# SilentStepStick-TMC5160_v14.net
KiCad netlist of a schematic drawn in EAGLE
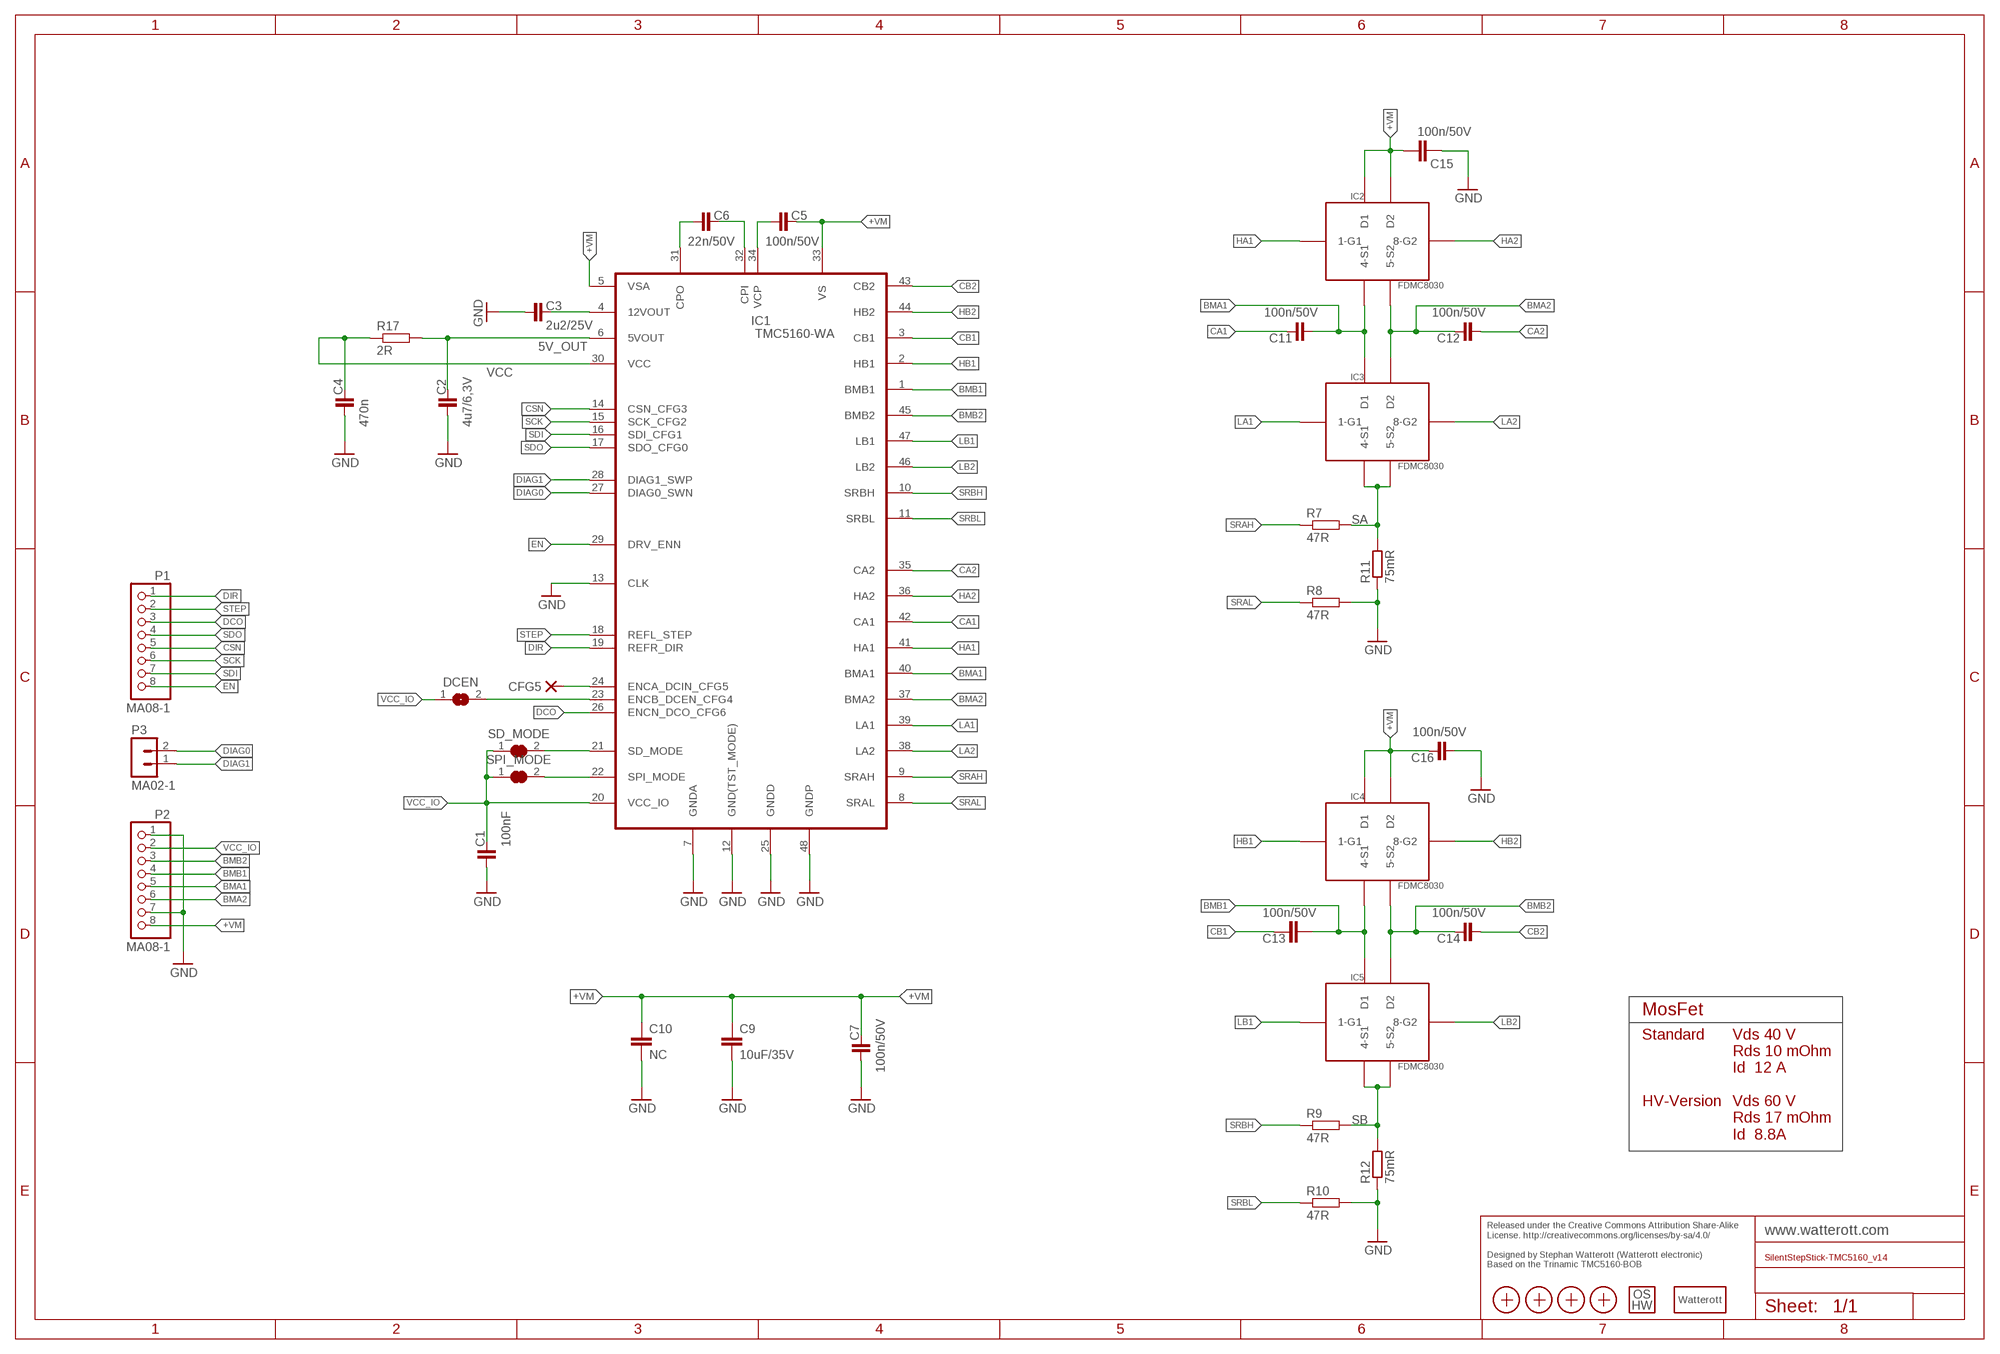
[diagram p0: schematic, sheet 1]

(export (version "E")
  (design (tool "Eeschema 10.0.6"))
  (components
    (comp (ref "C1")
      (value "100nF")
      (footprint "eagle-import:C0402")
      (libsource (lib "eagle-import") (part "CAPACITOR-0402"))
    )
    (comp (ref "C2")
      (value "4u7/6,3V")
      (footprint "eagle-import:C0402")
      (libsource (lib "eagle-import") (part "CAPACITOR-0402"))
    )
    (comp (ref "C3")
      (value "2u2/25V")
      (footprint "eagle-import:C0402")
      (libsource (lib "eagle-import") (part "CAPACITOR-0402"))
    )
    (comp (ref "C4")
      (value "470n")
      (footprint "eagle-import:C0402")
      (libsource (lib "eagle-import") (part "CAPACITOR-0402"))
    )
    (comp (ref "C5")
      (value "100n/50V")
      (footprint "eagle-import:C0402")
      (libsource (lib "eagle-import") (part "CAPACITOR-0402"))
    )
    (comp (ref "C6")
      (value "22n/50V")
      (footprint "eagle-import:C0402")
      (libsource (lib "eagle-import") (part "CAPACITOR-0402"))
    )
    (comp (ref "C7")
      (value "100n/50V")
      (footprint "eagle-import:C0402")
      (libsource (lib "eagle-import") (part "CAPACITOR-0402"))
    )
    (comp (ref "C9")
      (value "10uF/35V")
      (footprint "eagle-import:C0805")
      (libsource (lib "eagle-import") (part "C-EUC0805"))
    )
    (comp (ref "C10")
      (value "NC")
      (footprint "eagle-import:C0805")
      (libsource (lib "eagle-import") (part "C-EUC0805"))
    )
    (comp (ref "C11")
      (value "100n/50V")
      (footprint "eagle-import:C0402")
      (libsource (lib "eagle-import") (part "CAPACITOR-0402"))
    )
    (comp (ref "C12")
      (value "100n/50V")
      (footprint "eagle-import:C0402")
      (libsource (lib "eagle-import") (part "CAPACITOR-0402"))
    )
    (comp (ref "C13")
      (value "100n/50V")
      (footprint "eagle-import:C0402")
      (libsource (lib "eagle-import") (part "C-EUC0402"))
    )
    (comp (ref "C14")
      (value "100n/50V")
      (footprint "eagle-import:C0402")
      (libsource (lib "eagle-import") (part "CAPACITOR-0402"))
    )
    (comp (ref "C15")
      (value "100n/50V")
      (footprint "eagle-import:C0402")
      (libsource (lib "eagle-import") (part "C-EUC0402"))
    )
    (comp (ref "C16")
      (value "100n/50V")
      (footprint "eagle-import:C0402")
      (libsource (lib "eagle-import") (part "CAPACITOR-0402"))
    )
    (comp (ref "CFG5")
      (value "PAD-0.7_NC")
      (footprint "eagle-import:PAD-0.7_NC")
      (libsource (lib "eagle-import") (part "PAD-0.7_NC"))
    )
    (comp (ref "DCEN")
      (value "JUMPER2-0402-NC")
      (footprint "eagle-import:JUMPER2-0402_NC")
      (libsource (lib "eagle-import") (part "JUMPER2-0402-NC"))
    )
    (comp (ref "IC1")
      (value "TMC5160-WA")
      (footprint "eagle-import:VQFN56(47)_8.0X8.0X0.9MM_0.5P_EP")
      (libsource (lib "eagle-import") (part "TMC5160-WA"))
    )
    (comp (ref "IC2")
      (value "FDMC8030")
      (footprint "eagle-import:8-POWERWDFN")
      (libsource (lib "eagle-import") (part "FDMC8030"))
    )
    (comp (ref "IC3")
      (value "FDMC8030")
      (footprint "eagle-import:8-POWERWDFN")
      (libsource (lib "eagle-import") (part "FDMC8030"))
    )
    (comp (ref "IC4")
      (value "FDMC8030")
      (footprint "eagle-import:8-POWERWDFN")
      (libsource (lib "eagle-import") (part "FDMC8030"))
    )
    (comp (ref "IC5")
      (value "FDMC8030")
      (footprint "eagle-import:8-POWERWDFN")
      (libsource (lib "eagle-import") (part "FDMC8030"))
    )
    (comp (ref "LOGO1")
      (value "LOGO_SPARK-2")
      (footprint "eagle-import:SPARK_2MM")
      (libsource (lib "eagle-import") (part "LOGO_SPARK-2"))
    )
    (comp (ref "LOGO2")
      (value "LOGO_OSHW-2")
      (footprint "eagle-import:OSHW_2MM")
      (libsource (lib "eagle-import") (part "LOGO_OSHW-2"))
    )
    (comp (ref "P1")
      (value "MA08-1")
      (footprint "eagle-import:1X08-S")
      (libsource (lib "eagle-import") (part "PINHD-1X08_2.54-S"))
    )
    (comp (ref "P2")
      (value "MA08-1")
      (footprint "eagle-import:1X08-S")
      (libsource (lib "eagle-import") (part "PINHD-1X08_2.54-S"))
    )
    (comp (ref "P3")
      (value "MA02-1")
      (footprint "eagle-import:MA02-1")
      (libsource (lib "eagle-import") (part "MA02-1"))
    )
    (comp (ref "R7")
      (value "47R")
      (footprint "eagle-import:C0402")
      (libsource (lib "eagle-import") (part "RESISTOR-0402"))
    )
    (comp (ref "R8")
      (value "47R")
      (footprint "eagle-import:C0402")
      (libsource (lib "eagle-import") (part "RESISTOR-0402"))
    )
    (comp (ref "R9")
      (value "47R")
      (footprint "eagle-import:C0402")
      (libsource (lib "eagle-import") (part "RESISTOR-0402"))
    )
    (comp (ref "R10")
      (value "47R")
      (footprint "eagle-import:C0402")
      (libsource (lib "eagle-import") (part "RESISTOR-0402"))
    )
    (comp (ref "R11")
      (value "75mR")
      (footprint "eagle-import:R1206")
      (libsource (lib "eagle-import") (part "R-EU_R1206"))
    )
    (comp (ref "R12")
      (value "75mR")
      (footprint "eagle-import:R1206")
      (libsource (lib "eagle-import") (part "R-EU_R1206"))
    )
    (comp (ref "R17")
      (value "2R")
      (footprint "eagle-import:C0402")
      (libsource (lib "eagle-import") (part "RESISTOR-0402"))
    )
    (comp (ref "SD_MODE")
      (value "JUMPER2-0402-NC")
      (footprint "eagle-import:JUMPER2-0402_NC")
      (libsource (lib "eagle-import") (part "JUMPER2-0402-NC"))
    )
    (comp (ref "SPI_MODE")
      (value "JUMPER2-0402-NC")
      (footprint "eagle-import:JUMPER2-0402_NC")
      (libsource (lib "eagle-import") (part "JUMPER2-0402-NC"))
    )
    (comp (ref "X1")
      (value "PASSER-04")
      (footprint "eagle-import:PASSER_04MM")
      (libsource (lib "eagle-import") (part "PASSER-04"))
    )
    (comp (ref "X2")
      (value "PASSER-04")
      (footprint "eagle-import:PASSER_04MM")
      (libsource (lib "eagle-import") (part "PASSER-04"))
    )
    (comp (ref "X3")
      (value "PASSER-04")
      (footprint "eagle-import:PASSER_04MM")
      (libsource (lib "eagle-import") (part "PASSER-04"))
    )
    (comp (ref "X4")
      (value "PASSER-04")
      (footprint "eagle-import:PASSER_04MM")
      (libsource (lib "eagle-import") (part "PASSER-04"))
    )
  )
  (nets
    (net (code "1") (name "+VM") (class "Default")
      (node (ref "C10") (pin "1") (pinfunction "1_1") (pintype "passive"))
      (node (ref "C15") (pin "2") (pinfunction "2_2") (pintype "passive"))
      (node (ref "C16") (pin "2") (pinfunction "2_2") (pintype "passive"))
      (node (ref "C5") (pin "2") (pinfunction "2_2") (pintype "passive"))
      (node (ref "C7") (pin "2") (pinfunction "2_2") (pintype "passive"))
      (node (ref "C9") (pin "1") (pinfunction "1_1") (pintype "passive"))
      (node (ref "IC1") (pin "33") (pinfunction "VS_33") (pintype "power_in"))
      (node (ref "IC1") (pin "5") (pinfunction "VSA_5") (pintype "power_in"))
      (node (ref "IC2") (pin "P$D1") (pinfunction "D1_P$D1") (pintype "bidirectional"))
      (node (ref "IC2") (pin "P$D2") (pinfunction "D2_P$D2") (pintype "bidirectional"))
      (node (ref "IC4") (pin "P$D1") (pinfunction "D1_P$D1") (pintype "bidirectional"))
      (node (ref "IC4") (pin "P$D2") (pinfunction "D2_P$D2") (pintype "bidirectional"))
      (node (ref "P2") (pin "8") (pinfunction "8_8") (pintype "passive"))
    )
    (net (code "2") (name "/5V_OUT") (class "Default")
      (node (ref "C2") (pin "2") (pinfunction "2_2") (pintype "passive"))
      (node (ref "IC1") (pin "6") (pinfunction "5VOUT_6") (pintype "bidirectional"))
      (node (ref "R17") (pin "2") (pinfunction "2_2") (pintype "passive"))
    )
    (net (code "3") (name "/SA") (class "Default")
      (node (ref "IC3") (pin "P$4") (pinfunction "4-S1_P$4") (pintype "bidirectional"))
      (node (ref "IC3") (pin "P$5") (pinfunction "5-S2_P$5") (pintype "bidirectional"))
      (node (ref "R11") (pin "2") (pinfunction "2_2") (pintype "passive"))
      (node (ref "R7") (pin "2") (pinfunction "2_2") (pintype "passive"))
    )
    (net (code "4") (name "/SB") (class "Default")
      (node (ref "IC5") (pin "P$4") (pinfunction "4-S1_P$4") (pintype "bidirectional"))
      (node (ref "IC5") (pin "P$5") (pinfunction "5-S2_P$5") (pintype "bidirectional"))
      (node (ref "R12") (pin "2") (pinfunction "2_2") (pintype "passive"))
      (node (ref "R9") (pin "2") (pinfunction "2_2") (pintype "passive"))
    )
    (net (code "5") (name "/VCC") (class "Default")
      (node (ref "C4") (pin "2") (pinfunction "2_2") (pintype "passive"))
      (node (ref "IC1") (pin "30") (pinfunction "VCC_30") (pintype "power_in"))
      (node (ref "R17") (pin "1") (pinfunction "1_1") (pintype "passive"))
    )
    (net (code "6") (name "BMA1") (class "Default")
      (node (ref "C11") (pin "1") (pinfunction "1_1") (pintype "passive"))
      (node (ref "IC1") (pin "40") (pinfunction "BMA1_40") (pintype "input"))
      (node (ref "IC2") (pin "P$4") (pinfunction "4-S1_P$4") (pintype "bidirectional"))
      (node (ref "IC3") (pin "P$D1") (pinfunction "D1_P$D1") (pintype "bidirectional"))
      (node (ref "P2") (pin "5") (pinfunction "5_5") (pintype "passive"))
    )
    (net (code "7") (name "BMA2") (class "Default")
      (node (ref "C12") (pin "2") (pinfunction "2_2") (pintype "passive"))
      (node (ref "IC1") (pin "37") (pinfunction "BMA2_37") (pintype "input"))
      (node (ref "IC2") (pin "P$5") (pinfunction "5-S2_P$5") (pintype "bidirectional"))
      (node (ref "IC3") (pin "P$D2") (pinfunction "D2_P$D2") (pintype "bidirectional"))
      (node (ref "P2") (pin "6") (pinfunction "6_6") (pintype "passive"))
    )
    (net (code "8") (name "BMB1") (class "Default")
      (node (ref "C13") (pin "1") (pinfunction "1_1") (pintype "passive"))
      (node (ref "IC1") (pin "1") (pinfunction "BMB1_1") (pintype "input"))
      (node (ref "IC4") (pin "P$4") (pinfunction "4-S1_P$4") (pintype "bidirectional"))
      (node (ref "IC5") (pin "P$D1") (pinfunction "D1_P$D1") (pintype "bidirectional"))
      (node (ref "P2") (pin "4") (pinfunction "4_4") (pintype "passive"))
    )
    (net (code "9") (name "BMB2") (class "Default")
      (node (ref "C14") (pin "2") (pinfunction "2_2") (pintype "passive"))
      (node (ref "IC1") (pin "45") (pinfunction "BMB2_45") (pintype "input"))
      (node (ref "IC4") (pin "P$5") (pinfunction "5-S2_P$5") (pintype "bidirectional"))
      (node (ref "IC5") (pin "P$D2") (pinfunction "D2_P$D2") (pintype "bidirectional"))
      (node (ref "P2") (pin "3") (pinfunction "3_3") (pintype "passive"))
    )
    (net (code "10") (name "CA1") (class "Default")
      (node (ref "C11") (pin "2") (pinfunction "2_2") (pintype "passive"))
      (node (ref "IC1") (pin "42") (pinfunction "CA1_42") (pintype "input"))
    )
    (net (code "11") (name "CA2") (class "Default")
      (node (ref "C12") (pin "1") (pinfunction "1_1") (pintype "passive"))
      (node (ref "IC1") (pin "35") (pinfunction "CA2_35") (pintype "input"))
    )
    (net (code "12") (name "CB1") (class "Default")
      (node (ref "C13") (pin "2") (pinfunction "2_2") (pintype "passive"))
      (node (ref "IC1") (pin "3") (pinfunction "CB1_3") (pintype "input"))
    )
    (net (code "13") (name "CB2") (class "Default")
      (node (ref "C14") (pin "1") (pinfunction "1_1") (pintype "passive"))
      (node (ref "IC1") (pin "43") (pinfunction "CB2_43") (pintype "input"))
    )
    (net (code "14") (name "CSN") (class "Default")
      (node (ref "IC1") (pin "14") (pinfunction "CSN_CFG3_14") (pintype "input"))
      (node (ref "P1") (pin "5") (pinfunction "5_5") (pintype "passive"))
    )
    (net (code "15") (name "DCO") (class "Default")
      (node (ref "IC1") (pin "26") (pinfunction "ENCN_DCO_CFG6_26") (pintype "bidirectional"))
      (node (ref "P1") (pin "3") (pinfunction "3_3") (pintype "passive"))
    )
    (net (code "16") (name "DIAG0") (class "Default")
      (node (ref "IC1") (pin "27") (pinfunction "DIAG0_SWN_27") (pintype "bidirectional"))
      (node (ref "P3") (pin "2") (pinfunction "2_2") (pintype "passive"))
    )
    (net (code "17") (name "DIAG1") (class "Default")
      (node (ref "IC1") (pin "28") (pinfunction "DIAG1_SWP_28") (pintype "bidirectional"))
      (node (ref "P3") (pin "1") (pinfunction "1_1") (pintype "passive"))
    )
    (net (code "18") (name "DIR") (class "Default")
      (node (ref "IC1") (pin "19") (pinfunction "REFR_DIR_19") (pintype "input"))
      (node (ref "P1") (pin "1") (pinfunction "1_1") (pintype "passive"))
    )
    (net (code "19") (name "EN") (class "Default")
      (node (ref "IC1") (pin "29") (pinfunction "DRV_ENN_29") (pintype "input"))
      (node (ref "P1") (pin "8") (pinfunction "8_8") (pintype "passive"))
    )
    (net (code "20") (name "GND") (class "Default")
      (node (ref "C1") (pin "1") (pinfunction "1_1") (pintype "passive"))
      (node (ref "C10") (pin "2") (pinfunction "2_2") (pintype "passive"))
      (node (ref "C15") (pin "1") (pinfunction "1_1") (pintype "passive"))
      (node (ref "C16") (pin "1") (pinfunction "1_1") (pintype "passive"))
      (node (ref "C2") (pin "1") (pinfunction "1_1") (pintype "passive"))
      (node (ref "C3") (pin "1") (pinfunction "1_1") (pintype "passive"))
      (node (ref "C4") (pin "1") (pinfunction "1_1") (pintype "passive"))
      (node (ref "C7") (pin "1") (pinfunction "1_1") (pintype "passive"))
      (node (ref "C9") (pin "2") (pinfunction "2_2") (pintype "passive"))
      (node (ref "IC1") (pin "12") (pinfunction "GND(TST_MODE)_12") (pintype "input"))
      (node (ref "IC1") (pin "13") (pinfunction "CLK_13") (pintype "input"))
      (node (ref "IC1") (pin "25") (pinfunction "GNDD_25") (pintype "power_in"))
      (node (ref "IC1") (pin "48") (pinfunction "GNDP_48") (pintype "power_in"))
      (node (ref "IC1") (pin "7") (pinfunction "GNDA_7") (pintype "power_in"))
      (node (ref "P2") (pin "1") (pinfunction "1_1") (pintype "passive"))
      (node (ref "P2") (pin "7") (pinfunction "7_7") (pintype "passive"))
      (node (ref "R10") (pin "2") (pinfunction "2_2") (pintype "passive"))
      (node (ref "R11") (pin "1") (pinfunction "1_1") (pintype "passive"))
      (node (ref "R12") (pin "1") (pinfunction "1_1") (pintype "passive"))
      (node (ref "R8") (pin "2") (pinfunction "2_2") (pintype "passive"))
    )
    (net (code "21") (name "HA1") (class "Default")
      (node (ref "IC1") (pin "41") (pinfunction "HA1_41") (pintype "output"))
      (node (ref "IC2") (pin "P$1") (pinfunction "1-G1_P$1") (pintype "bidirectional"))
    )
    (net (code "22") (name "HA2") (class "Default")
      (node (ref "IC1") (pin "36") (pinfunction "HA2_36") (pintype "output"))
      (node (ref "IC2") (pin "P$8") (pinfunction "8-G2_P$8") (pintype "bidirectional"))
    )
    (net (code "23") (name "HB1") (class "Default")
      (node (ref "IC1") (pin "2") (pinfunction "HB1_2") (pintype "output"))
      (node (ref "IC4") (pin "P$1") (pinfunction "1-G1_P$1") (pintype "bidirectional"))
    )
    (net (code "24") (name "HB2") (class "Default")
      (node (ref "IC1") (pin "44") (pinfunction "HB2_44") (pintype "output"))
      (node (ref "IC4") (pin "P$8") (pinfunction "8-G2_P$8") (pintype "bidirectional"))
    )
    (net (code "25") (name "LA1") (class "Default")
      (node (ref "IC1") (pin "39") (pinfunction "LA1_39") (pintype "output"))
      (node (ref "IC3") (pin "P$1") (pinfunction "1-G1_P$1") (pintype "bidirectional"))
    )
    (net (code "26") (name "LA2") (class "Default")
      (node (ref "IC1") (pin "38") (pinfunction "LA2_38") (pintype "output"))
      (node (ref "IC3") (pin "P$8") (pinfunction "8-G2_P$8") (pintype "bidirectional"))
    )
    (net (code "27") (name "LB1") (class "Default")
      (node (ref "IC1") (pin "47") (pinfunction "LB1_47") (pintype "output"))
      (node (ref "IC5") (pin "P$1") (pinfunction "1-G1_P$1") (pintype "bidirectional"))
    )
    (net (code "28") (name "LB2") (class "Default")
      (node (ref "IC1") (pin "46") (pinfunction "LB2_46") (pintype "output"))
      (node (ref "IC5") (pin "P$8") (pinfunction "8-G2_P$8") (pintype "bidirectional"))
    )
    (net (code "29") (name "Net-(CFG5-P)") (class "Default")
      (node (ref "CFG5") (pin "1") (pinfunction "P_1") (pintype "passive"))
      (node (ref "IC1") (pin "24") (pinfunction "ENCA_DCIN_CFG5_24") (pintype "input"))
    )
    (net (code "30") (name "Net-(IC1-12VOUT)") (class "Default")
      (node (ref "C3") (pin "2") (pinfunction "2_2") (pintype "passive"))
      (node (ref "IC1") (pin "4") (pinfunction "12VOUT_4") (pintype "bidirectional"))
    )
    (net (code "31") (name "Net-(IC1-CPI)") (class "Default")
      (node (ref "C6") (pin "2") (pinfunction "2_2") (pintype "passive"))
      (node (ref "IC1") (pin "32") (pinfunction "CPI_32") (pintype "input"))
    )
    (net (code "32") (name "Net-(IC1-CPO)") (class "Default")
      (node (ref "C6") (pin "1") (pinfunction "1_1") (pintype "passive"))
      (node (ref "IC1") (pin "31") (pinfunction "CPO_31") (pintype "input"))
    )
    (net (code "33") (name "Net-(IC1-ENCB_DCEN_CFG4)") (class "Default")
      (node (ref "DCEN") (pin "2") (pinfunction "2_2") (pintype "passive"))
      (node (ref "IC1") (pin "23") (pinfunction "ENCB_DCEN_CFG4_23") (pintype "input"))
    )
    (net (code "34") (name "Net-(IC1-SD_MODE)") (class "Default")
      (node (ref "IC1") (pin "21") (pinfunction "SD_MODE_21") (pintype "input"))
      (node (ref "SD_MODE") (pin "2") (pinfunction "2_2") (pintype "passive"))
    )
    (net (code "35") (name "Net-(IC1-SPI_MODE)") (class "Default")
      (node (ref "IC1") (pin "22") (pinfunction "SPI_MODE_22") (pintype "input"))
      (node (ref "SPI_MODE") (pin "2") (pinfunction "2_2") (pintype "passive"))
    )
    (net (code "36") (name "Net-(IC1-VCP)") (class "Default")
      (node (ref "C5") (pin "1") (pinfunction "1_1") (pintype "passive"))
      (node (ref "IC1") (pin "34") (pinfunction "VCP_34") (pintype "input"))
    )
    (net (code "37") (name "SCK") (class "Default")
      (node (ref "IC1") (pin "15") (pinfunction "SCK_CFG2_15") (pintype "input"))
      (node (ref "P1") (pin "6") (pinfunction "6_6") (pintype "passive"))
    )
    (net (code "38") (name "SDI") (class "Default")
      (node (ref "IC1") (pin "16") (pinfunction "SDI_CFG1_16") (pintype "input"))
      (node (ref "P1") (pin "7") (pinfunction "7_7") (pintype "passive"))
    )
    (net (code "39") (name "SDO") (class "Default")
      (node (ref "IC1") (pin "17") (pinfunction "SDO_CFG0_17") (pintype "bidirectional"))
      (node (ref "P1") (pin "4") (pinfunction "4_4") (pintype "passive"))
    )
    (net (code "40") (name "SRAH") (class "Default")
      (node (ref "IC1") (pin "9") (pinfunction "SRAH_9") (pintype "input"))
      (node (ref "R7") (pin "1") (pinfunction "1_1") (pintype "passive"))
    )
    (net (code "41") (name "SRAL") (class "Default")
      (node (ref "IC1") (pin "8") (pinfunction "SRAL_8") (pintype "input"))
      (node (ref "R8") (pin "1") (pinfunction "1_1") (pintype "passive"))
    )
    (net (code "42") (name "SRBH") (class "Default")
      (node (ref "IC1") (pin "10") (pinfunction "SRBH_10") (pintype "input"))
      (node (ref "R9") (pin "1") (pinfunction "1_1") (pintype "passive"))
    )
    (net (code "43") (name "SRBL") (class "Default")
      (node (ref "IC1") (pin "11") (pinfunction "SRBL_11") (pintype "input"))
      (node (ref "R10") (pin "1") (pinfunction "1_1") (pintype "passive"))
    )
    (net (code "44") (name "STEP") (class "Default")
      (node (ref "IC1") (pin "18") (pinfunction "REFL_STEP_18") (pintype "input"))
      (node (ref "P1") (pin "2") (pinfunction "2_2") (pintype "passive"))
    )
    (net (code "45") (name "VCC_IO") (class "Default")
      (node (ref "C1") (pin "2") (pinfunction "2_2") (pintype "passive"))
      (node (ref "DCEN") (pin "1") (pinfunction "1_1") (pintype "passive"))
      (node (ref "IC1") (pin "20") (pinfunction "VCC_IO_20") (pintype "power_in"))
      (node (ref "P2") (pin "2") (pinfunction "2_2") (pintype "passive"))
      (node (ref "SD_MODE") (pin "1") (pinfunction "1_1") (pintype "passive"))
      (node (ref "SPI_MODE") (pin "1") (pinfunction "1_1") (pintype "passive"))
    )
  )
)
